# tick-mk-5_1.net
KiCad netlist of a schematic drawn in EAGLE
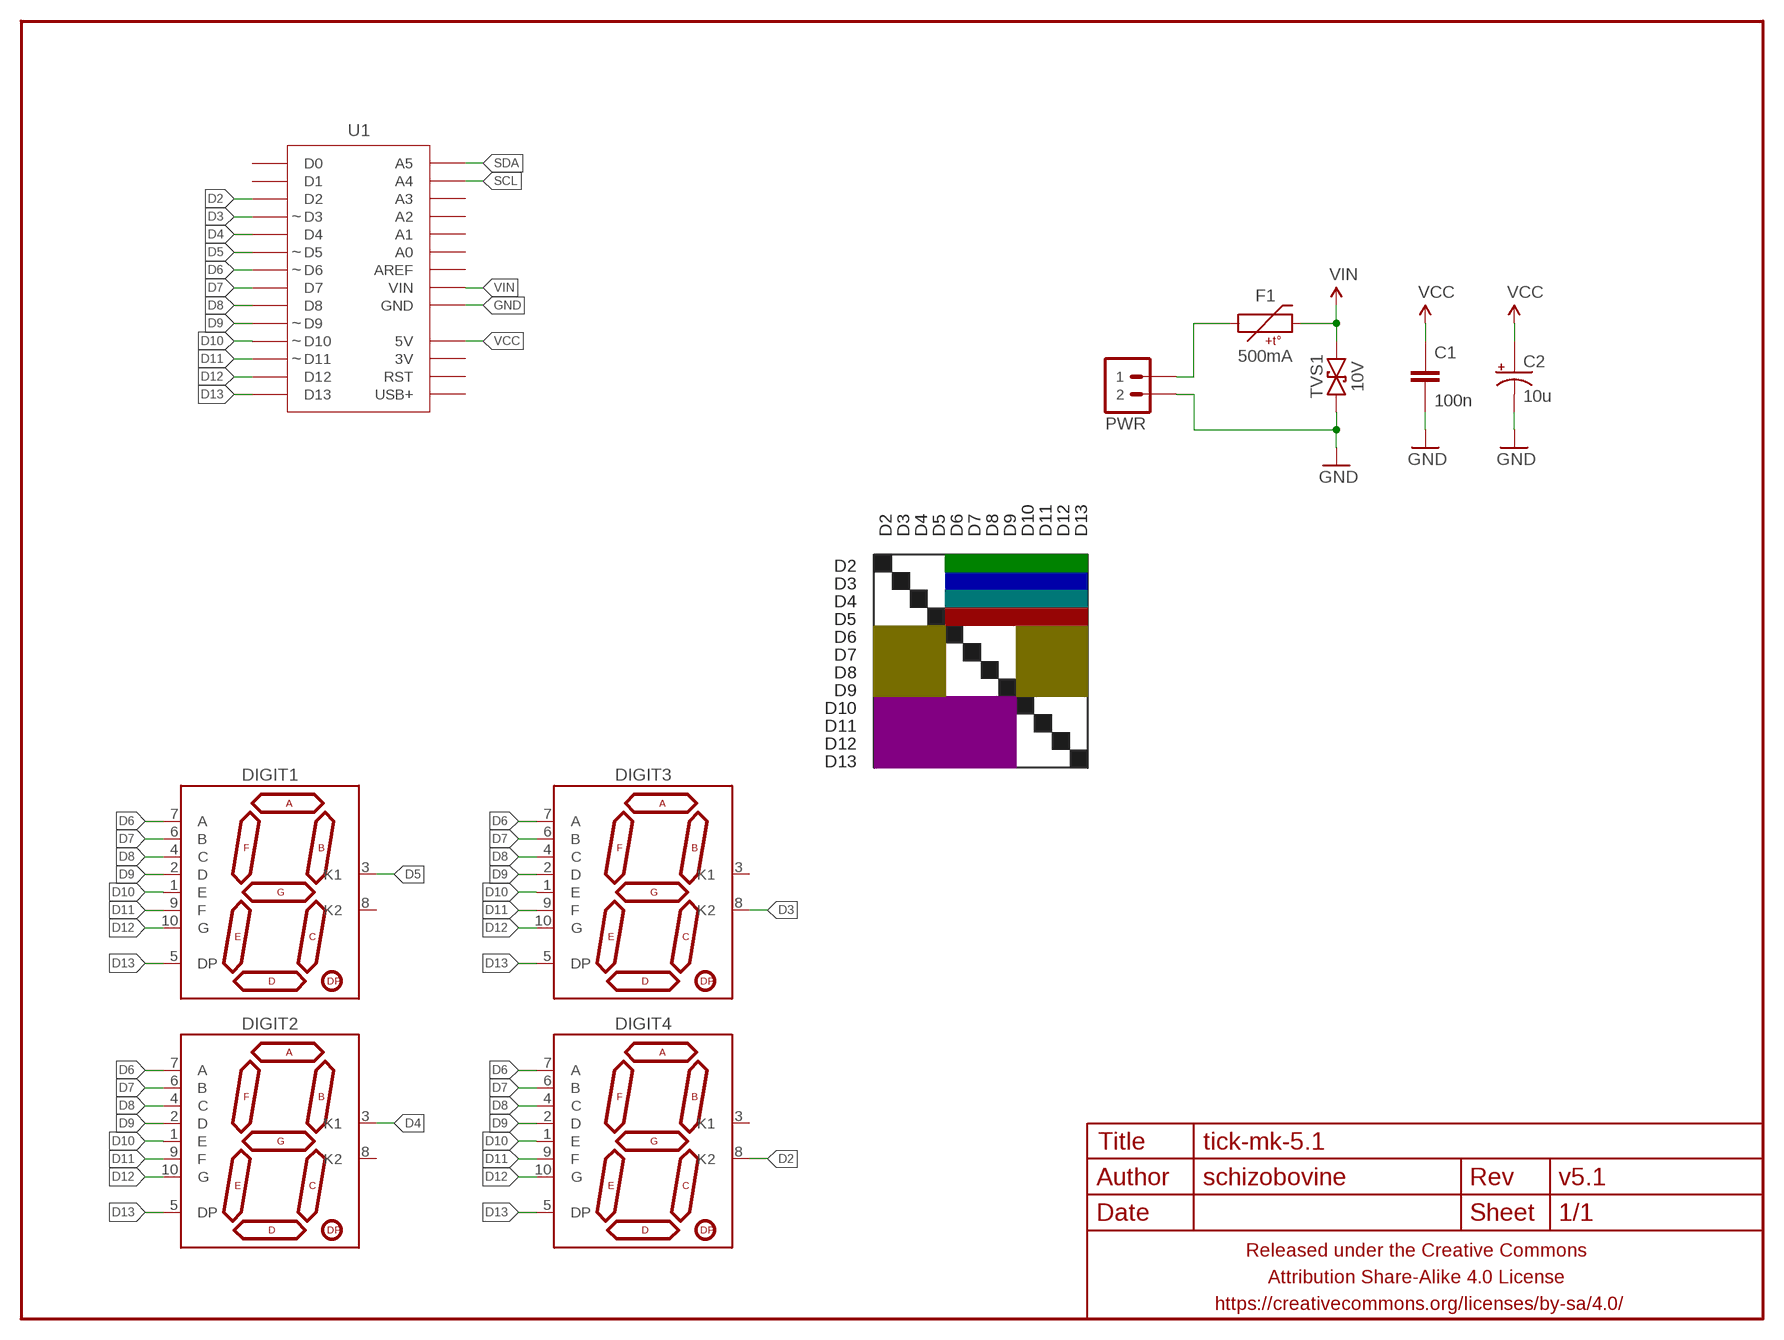
[diagram p0: schematic, sheet 1]

(export (version "E")
  (design (tool "Eeschema 10.0.6"))
  (components
    (comp (ref "C1")
      (value "100n")
      (footprint "eagle-import:C025-024X044")
      (libsource (lib "eagle-import") (part "CAPACITOR-CERAMIC025-024X044"))
    )
    (comp (ref "C2")
      (value "10u")
      (footprint "eagle-import:E2-5")
      (libsource (lib "eagle-import") (part "CAPACITOR-POLARIZEDE2-5"))
    )
    (comp (ref "DIGIT1")
      (value "7SEG_1DIGPTH-25.4MM-BARE")
      (footprint "eagle-import:7SEG_1DIG_25.4MM_NOSILK")
      (libsource (lib "eagle-import") (part "7SEG_1DIGPTH-25.4MM-BARE"))
    )
    (comp (ref "DIGIT2")
      (value "7SEG_1DIGPTH-25.4MM-BARE")
      (footprint "eagle-import:7SEG_1DIG_25.4MM_NOSILK")
      (libsource (lib "eagle-import") (part "7SEG_1DIGPTH-25.4MM-BARE"))
    )
    (comp (ref "DIGIT3")
      (value "7SEG_1DIGPTH-25.4MM-BARE")
      (footprint "eagle-import:7SEG_1DIG_25.4MM_NOSILK")
      (libsource (lib "eagle-import") (part "7SEG_1DIGPTH-25.4MM-BARE"))
    )
    (comp (ref "DIGIT4")
      (value "7SEG_1DIGPTH-25.4MM-BARE")
      (footprint "eagle-import:7SEG_1DIG_25.4MM_NOSILK")
      (libsource (lib "eagle-import") (part "7SEG_1DIGPTH-25.4MM-BARE"))
    )
    (comp (ref "F1")
      (value "500mA")
      (footprint "eagle-import:PTC-PTH-5.08MM")
      (libsource (lib "eagle-import") (part "PTCPTH-5.08MM"))
    )
    (comp (ref "FRAME1")
      (value "FRAME-LETTERNO_PACKAGE")
      (footprint "eagle-import:DUMMY")
      (fields (field (name "DESIGNER") "schizobovine") (field (name "VERSION") "v5.1"))
      (libsource (lib "eagle-import") (part "FRAME-LETTERNO_PACKAGE"))
    )
    (comp (ref "PWR")
      (value "M02JST-PTH-VERT")
      (footprint "eagle-import:JST-2-PH-VERT-PTH")
      (libsource (lib "eagle-import") (part "M02JST-PTH-VERT"))
    )
    (comp (ref "TVS1")
      (value "10V")
      (footprint "eagle-import:DO-41-TVS-BI-10.16MM")
      (libsource (lib "eagle-import") (part "TVSDO-41-10.16MM"))
    )
    (comp (ref "U1")
      (value "ADAFRUIT_METRO_MININOHOLES-NOOUTLINE-SILK")
      (footprint "eagle-import:ADAFRUIT_METRO_MINI")
      (libsource (lib "eagle-import") (part "ADAFRUIT_METRO_MININOHOLES-NOOUTLINE-SILK"))
    )
  )
  (nets
    (net (code "1") (name "D2") (class "Default")
      (node (ref "DIGIT4") (pin "8") (pinfunction "K2_8") (pintype "bidirectional"))
      (node (ref "U1") (pin "3") (pinfunction "D2_3") (pintype "bidirectional"))
    )
    (net (code "2") (name "D3") (class "Default")
      (node (ref "DIGIT3") (pin "8") (pinfunction "K2_8") (pintype "bidirectional"))
      (node (ref "U1") (pin "4") (pinfunction "D3_4") (pintype "bidirectional"))
    )
    (net (code "3") (name "D4") (class "Default")
      (node (ref "DIGIT2") (pin "3") (pinfunction "K1_3") (pintype "bidirectional"))
      (node (ref "U1") (pin "5") (pinfunction "D4_5") (pintype "bidirectional"))
    )
    (net (code "4") (name "D5") (class "Default")
      (node (ref "DIGIT1") (pin "3") (pinfunction "K1_3") (pintype "bidirectional"))
      (node (ref "U1") (pin "6") (pinfunction "D5_6") (pintype "bidirectional"))
    )
    (net (code "5") (name "D6") (class "Default")
      (node (ref "DIGIT1") (pin "7") (pinfunction "A_7") (pintype "bidirectional"))
      (node (ref "DIGIT2") (pin "7") (pinfunction "A_7") (pintype "bidirectional"))
      (node (ref "DIGIT3") (pin "7") (pinfunction "A_7") (pintype "bidirectional"))
      (node (ref "DIGIT4") (pin "7") (pinfunction "A_7") (pintype "bidirectional"))
      (node (ref "U1") (pin "7") (pinfunction "D6_7") (pintype "bidirectional"))
    )
    (net (code "6") (name "D7") (class "Default")
      (node (ref "DIGIT1") (pin "6") (pinfunction "B_6") (pintype "bidirectional"))
      (node (ref "DIGIT2") (pin "6") (pinfunction "B_6") (pintype "bidirectional"))
      (node (ref "DIGIT3") (pin "6") (pinfunction "B_6") (pintype "bidirectional"))
      (node (ref "DIGIT4") (pin "6") (pinfunction "B_6") (pintype "bidirectional"))
      (node (ref "U1") (pin "8") (pinfunction "D7_8") (pintype "bidirectional"))
    )
    (net (code "7") (name "D8") (class "Default")
      (node (ref "DIGIT1") (pin "4") (pinfunction "C_4") (pintype "bidirectional"))
      (node (ref "DIGIT2") (pin "4") (pinfunction "C_4") (pintype "bidirectional"))
      (node (ref "DIGIT3") (pin "4") (pinfunction "C_4") (pintype "bidirectional"))
      (node (ref "DIGIT4") (pin "4") (pinfunction "C_4") (pintype "bidirectional"))
      (node (ref "U1") (pin "9") (pinfunction "D8_9") (pintype "bidirectional"))
    )
    (net (code "8") (name "D9") (class "Default")
      (node (ref "DIGIT1") (pin "2") (pinfunction "D_2") (pintype "bidirectional"))
      (node (ref "DIGIT2") (pin "2") (pinfunction "D_2") (pintype "bidirectional"))
      (node (ref "DIGIT3") (pin "2") (pinfunction "D_2") (pintype "bidirectional"))
      (node (ref "DIGIT4") (pin "2") (pinfunction "D_2") (pintype "bidirectional"))
      (node (ref "U1") (pin "10") (pinfunction "D9_10") (pintype "bidirectional"))
    )
    (net (code "9") (name "D10") (class "Default")
      (node (ref "DIGIT1") (pin "1") (pinfunction "E_1") (pintype "bidirectional"))
      (node (ref "DIGIT2") (pin "1") (pinfunction "E_1") (pintype "bidirectional"))
      (node (ref "DIGIT3") (pin "1") (pinfunction "E_1") (pintype "bidirectional"))
      (node (ref "DIGIT4") (pin "1") (pinfunction "E_1") (pintype "bidirectional"))
      (node (ref "U1") (pin "11") (pinfunction "D10_11") (pintype "bidirectional"))
    )
    (net (code "10") (name "D11") (class "Default")
      (node (ref "DIGIT1") (pin "9") (pinfunction "F_9") (pintype "bidirectional"))
      (node (ref "DIGIT2") (pin "9") (pinfunction "F_9") (pintype "bidirectional"))
      (node (ref "DIGIT3") (pin "9") (pinfunction "F_9") (pintype "bidirectional"))
      (node (ref "DIGIT4") (pin "9") (pinfunction "F_9") (pintype "bidirectional"))
      (node (ref "U1") (pin "12") (pinfunction "D11_12") (pintype "bidirectional"))
    )
    (net (code "11") (name "D12") (class "Default")
      (node (ref "DIGIT1") (pin "10") (pinfunction "G_10") (pintype "bidirectional"))
      (node (ref "DIGIT2") (pin "10") (pinfunction "G_10") (pintype "bidirectional"))
      (node (ref "DIGIT3") (pin "10") (pinfunction "G_10") (pintype "bidirectional"))
      (node (ref "DIGIT4") (pin "10") (pinfunction "G_10") (pintype "bidirectional"))
      (node (ref "U1") (pin "13") (pinfunction "D12_13") (pintype "bidirectional"))
    )
    (net (code "12") (name "D13") (class "Default")
      (node (ref "DIGIT1") (pin "5") (pinfunction "DP_5") (pintype "bidirectional"))
      (node (ref "DIGIT2") (pin "5") (pinfunction "DP_5") (pintype "bidirectional"))
      (node (ref "DIGIT3") (pin "5") (pinfunction "DP_5") (pintype "bidirectional"))
      (node (ref "DIGIT4") (pin "5") (pinfunction "DP_5") (pintype "bidirectional"))
      (node (ref "U1") (pin "14") (pinfunction "D13_14") (pintype "bidirectional"))
    )
    (net (code "13") (name "GND") (class "Default")
      (node (ref "C1") (pin "2") (pinfunction "2_2") (pintype "passive"))
      (node (ref "C2") (pin "-") (pinfunction "-_-") (pintype "passive"))
      (node (ref "PWR") (pin "2") (pinfunction "2_2") (pintype "passive"))
      (node (ref "TVS1") (pin "P$1") (pinfunction "1_P$1") (pintype "passive"))
      (node (ref "U1") (pin "19") (pinfunction "GND_19") (pintype "bidirectional"))
      (node (ref "U1") (pin "20") (pinfunction "GND_20") (pintype "bidirectional"))
    )
    (net (code "14") (name "Net-(F1-1)") (class "Default")
      (node (ref "F1") (pin "P$1") (pinfunction "1_P$1") (pintype "passive"))
      (node (ref "PWR") (pin "1") (pinfunction "1_1") (pintype "passive"))
    )
    (net (code "15") (name "SCL") (class "Default")
      (node (ref "U1") (pin "27") (pinfunction "A4_27") (pintype "bidirectional"))
    )
    (net (code "16") (name "SDA") (class "Default")
      (node (ref "U1") (pin "28") (pinfunction "A5_28") (pintype "bidirectional"))
    )
    (net (code "17") (name "VCC") (class "Default")
      (node (ref "C1") (pin "1") (pinfunction "1_1") (pintype "passive"))
      (node (ref "C2") (pin "+") (pinfunction "+_+") (pintype "passive"))
      (node (ref "U1") (pin "18") (pinfunction "5V_18") (pintype "bidirectional"))
    )
    (net (code "18") (name "VIN") (class "Default")
      (node (ref "F1") (pin "P$2") (pinfunction "2_P$2") (pintype "passive"))
      (node (ref "TVS1") (pin "P$2") (pinfunction "2_P$2") (pintype "passive"))
      (node (ref "U1") (pin "21") (pinfunction "VIN_21") (pintype "bidirectional"))
    )
    (net (code "19") (name "unconnected-(DIGIT1-K2-Pad8)") (class "Default")
      (node (ref "DIGIT1") (pin "8") (pinfunction "K2_8") (pintype "bidirectional"))
    )
    (net (code "20") (name "unconnected-(DIGIT2-K2-Pad8)") (class "Default")
      (node (ref "DIGIT2") (pin "8") (pinfunction "K2_8") (pintype "bidirectional"))
    )
    (net (code "21") (name "unconnected-(DIGIT3-K1-Pad3)") (class "Default")
      (node (ref "DIGIT3") (pin "3") (pinfunction "K1_3") (pintype "bidirectional"))
    )
    (net (code "22") (name "unconnected-(DIGIT4-K1-Pad3)") (class "Default")
      (node (ref "DIGIT4") (pin "3") (pinfunction "K1_3") (pintype "bidirectional"))
    )
    (net (code "23") (name "unconnected-(U1-3V-Pad17)") (class "Default")
      (node (ref "U1") (pin "17") (pinfunction "3V_17") (pintype "bidirectional"))
    )
    (net (code "24") (name "unconnected-(U1-A0-Pad23)") (class "Default")
      (node (ref "U1") (pin "23") (pinfunction "A0_23") (pintype "bidirectional"))
    )
    (net (code "25") (name "unconnected-(U1-A1-Pad24)") (class "Default")
      (node (ref "U1") (pin "24") (pinfunction "A1_24") (pintype "bidirectional"))
    )
    (net (code "26") (name "unconnected-(U1-A2-Pad25)") (class "Default")
      (node (ref "U1") (pin "25") (pinfunction "A2_25") (pintype "bidirectional"))
    )
    (net (code "27") (name "unconnected-(U1-A3-Pad26)") (class "Default")
      (node (ref "U1") (pin "26") (pinfunction "A3_26") (pintype "bidirectional"))
    )
    (net (code "28") (name "unconnected-(U1-AREF-Pad22)") (class "Default")
      (node (ref "U1") (pin "22") (pinfunction "AREF_22") (pintype "bidirectional"))
    )
    (net (code "29") (name "unconnected-(U1-D0-Pad1)") (class "Default")
      (node (ref "U1") (pin "1") (pinfunction "D0_1") (pintype "bidirectional"))
    )
    (net (code "30") (name "unconnected-(U1-D1-Pad2)") (class "Default")
      (node (ref "U1") (pin "2") (pinfunction "D1_2") (pintype "bidirectional"))
    )
    (net (code "31") (name "unconnected-(U1-RST-Pad16)") (class "Default")
      (node (ref "U1") (pin "16") (pinfunction "RST_16") (pintype "bidirectional"))
    )
    (net (code "32") (name "unconnected-(U1-USB+-Pad15)") (class "Default")
      (node (ref "U1") (pin "15") (pinfunction "USB+_15") (pintype "bidirectional"))
    )
  )
)
